# Microcontroller.net
KiCad netlist of a schematic drawn in Altium Designer
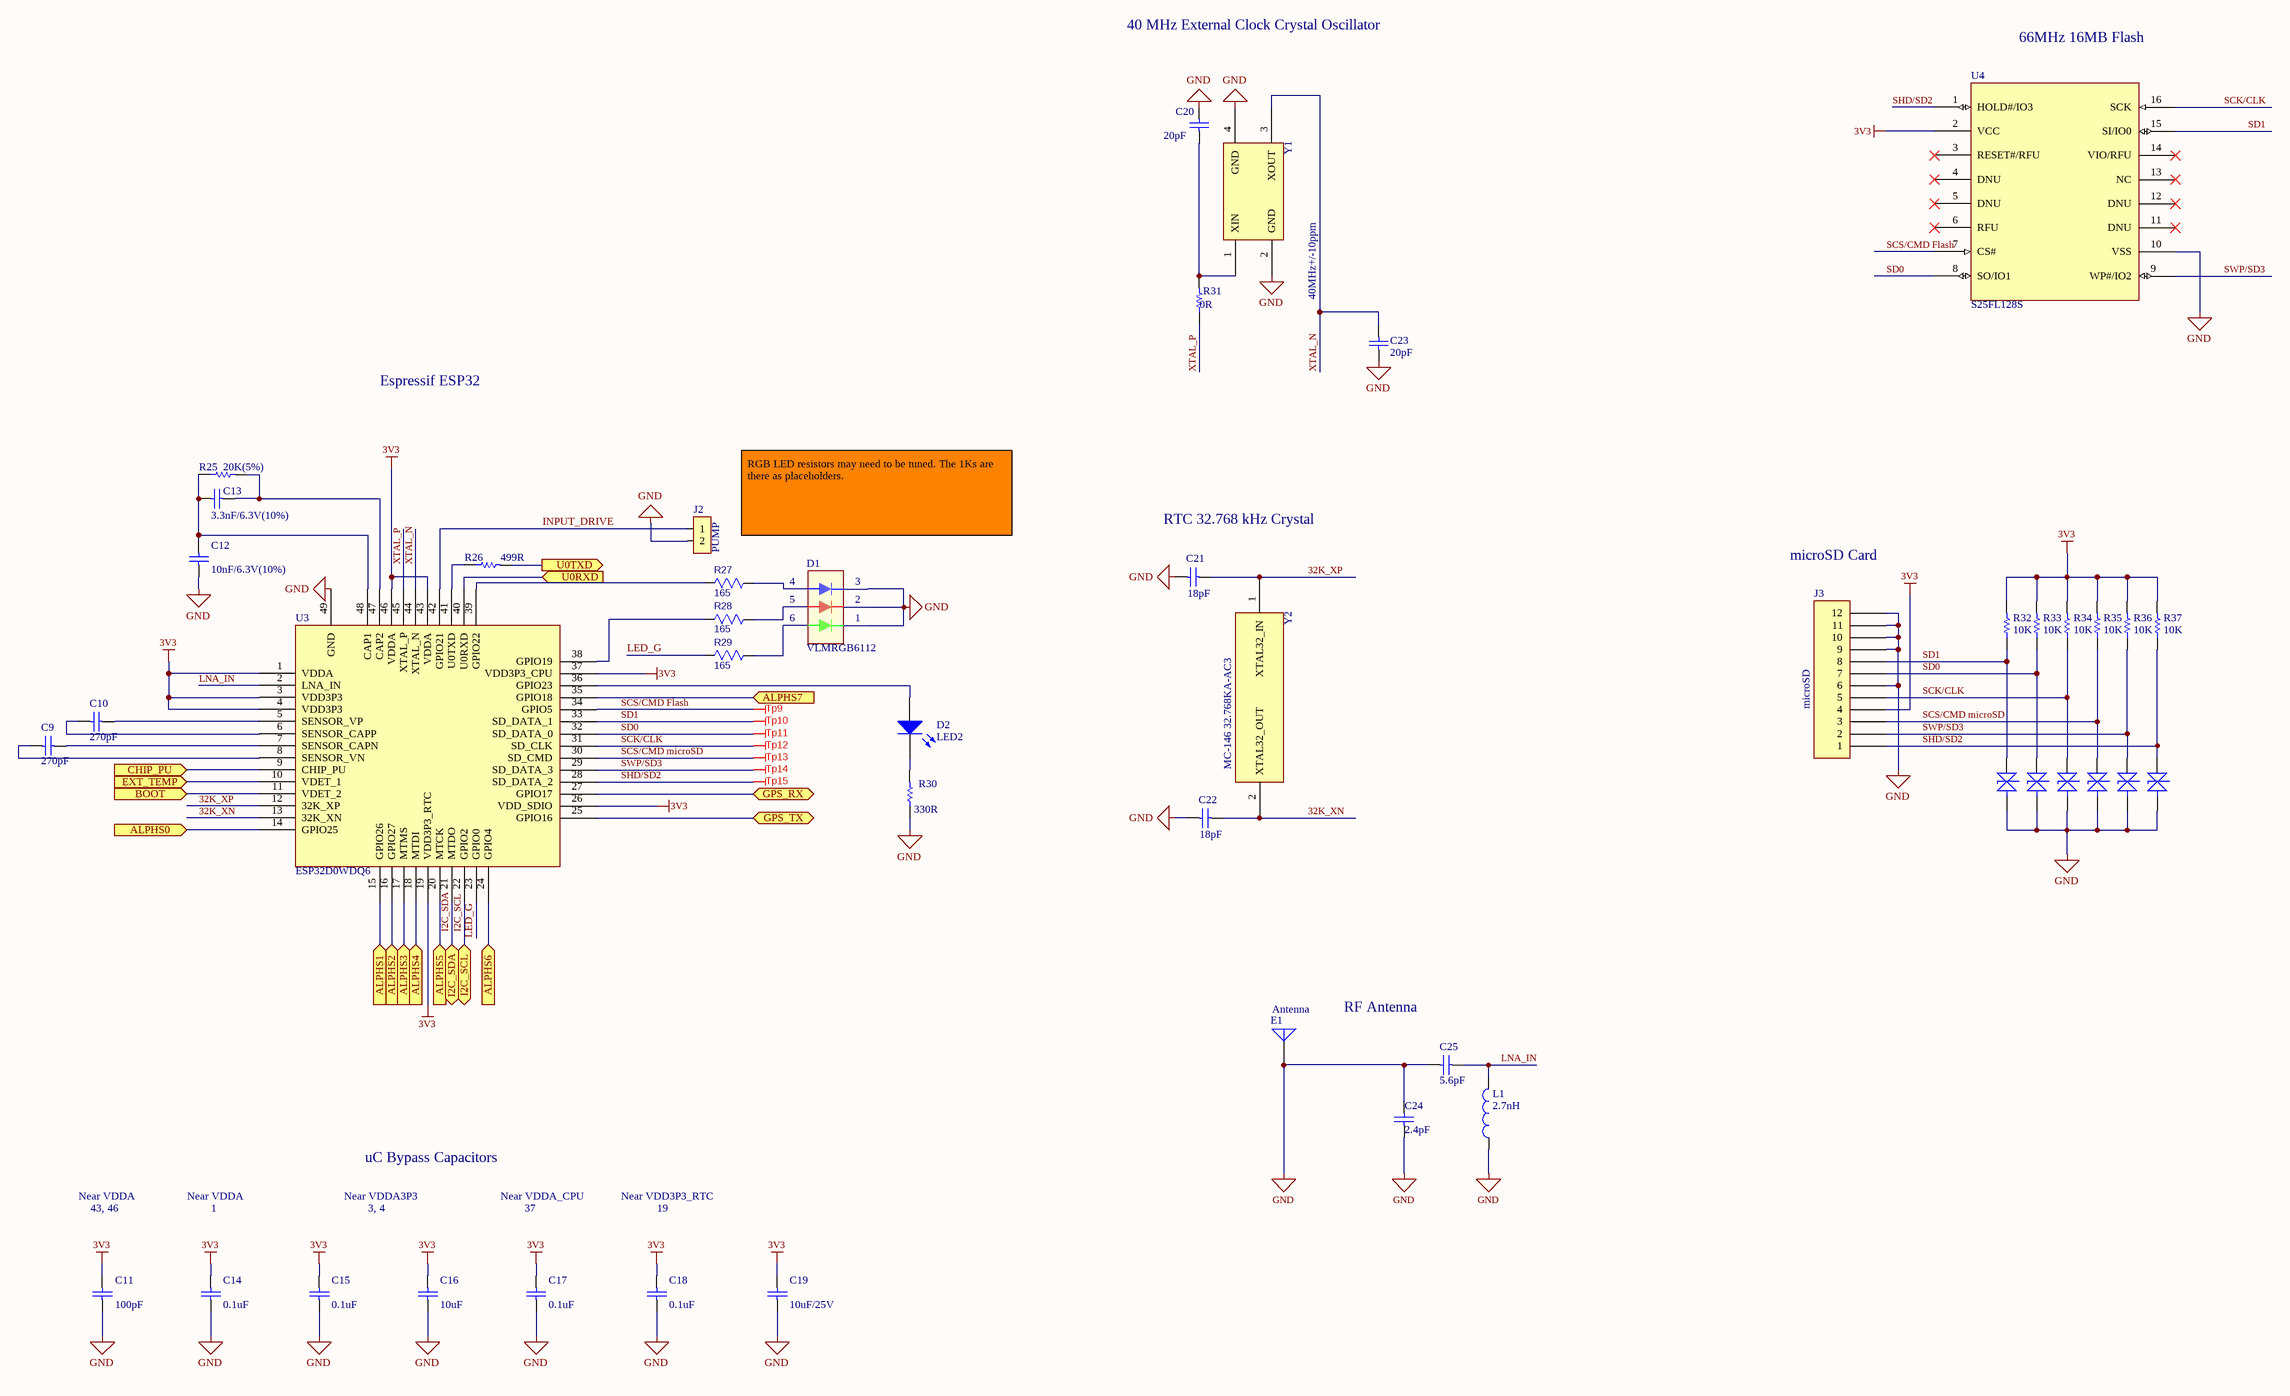
[diagram p0: Microcontroller.SchDoc]

(export (version "E")
  (design (tool "Eeschema 10.0.6"))
  (components
    (comp (ref "C9")
      (value "270pF")
      (footprint "1608[0603]")
      (description "Capacitor")
      (fields (field (name "Comment") "Cap") (field (name "PUBLISHER") "Altium Limited"))
      (libsource (lib "Miscellaneous Devices") (part "Cap"))
    )
    (comp (ref "C10")
      (value "270pF")
      (footprint "1608[0603]")
      (description "Capacitor")
      (fields (field (name "Comment") "Cap") (field (name "PUBLISHER") "Altium Limited"))
      (libsource (lib "Miscellaneous Devices") (part "Cap"))
    )
    (comp (ref "C11")
      (value "100pF")
      (footprint "1608[0603]")
      (description "Capacitor")
      (fields (field (name "Comment") "Cap") (field (name "PUBLISHER") "Altium Limited"))
      (libsource (lib "Miscellaneous Devices") (part "Cap"))
    )
    (comp (ref "C12")
      (value "10nF/6.3V(10%)")
      (footprint "1608[0603]")
      (description "Capacitor")
      (fields (field (name "Comment") "Cap") (field (name "PUBLISHER") "Altium Limited"))
      (libsource (lib "Miscellaneous Devices") (part "Cap"))
    )
    (comp (ref "C13")
      (value "3.3nF/6.3V(10%)")
      (footprint "1608[0603]")
      (description "Capacitor")
      (fields (field (name "Comment") "Cap") (field (name "PUBLISHER") "Altium Limited"))
      (libsource (lib "Miscellaneous Devices") (part "Cap"))
    )
    (comp (ref "C14")
      (value "0.1uF")
      (footprint "1608[0603]")
      (description "Capacitor")
      (fields (field (name "Comment") "Cap") (field (name "PUBLISHER") "Altium Limited"))
      (libsource (lib "Miscellaneous Devices") (part "Cap"))
    )
    (comp (ref "C15")
      (value "0.1uF")
      (footprint "1608[0603]")
      (description "Capacitor")
      (fields (field (name "Comment") "Cap") (field (name "PUBLISHER") "Altium Limited"))
      (libsource (lib "Miscellaneous Devices") (part "Cap"))
    )
    (comp (ref "C16")
      (value "10uF")
      (footprint "1608[0603]")
      (description "Capacitor")
      (fields (field (name "Comment") "Cap") (field (name "PUBLISHER") "Altium Limited"))
      (libsource (lib "Miscellaneous Devices") (part "Cap"))
    )
    (comp (ref "C17")
      (value "0.1uF")
      (footprint "1608[0603]")
      (description "Capacitor")
      (fields (field (name "Comment") "Cap") (field (name "PUBLISHER") "Altium Limited"))
      (libsource (lib "Miscellaneous Devices") (part "Cap"))
    )
    (comp (ref "C18")
      (value "0.1uF")
      (footprint "1608[0603]")
      (description "Capacitor")
      (fields (field (name "Comment") "Cap") (field (name "PUBLISHER") "Altium Limited"))
      (libsource (lib "Miscellaneous Devices") (part "Cap"))
    )
    (comp (ref "C19")
      (value "10uF/25V")
      (footprint "1608[0603]")
      (description "Capacitor")
      (fields (field (name "Comment") "Cap") (field (name "PUBLISHER") "Altium Limited"))
      (libsource (lib "Miscellaneous Devices") (part "Cap"))
    )
    (comp (ref "C20")
      (value "20pF")
      (footprint "1608[0603]")
      (description "Capacitor")
      (fields (field (name "Comment") "Cap") (field (name "PUBLISHER") "Altium Limited"))
      (libsource (lib "Miscellaneous Devices") (part "Cap"))
    )
    (comp (ref "C21")
      (value "18pF")
      (footprint "1608[0603]")
      (description "Capacitor")
      (fields (field (name "Comment") "Cap") (field (name "PUBLISHER") "Altium Limited"))
      (libsource (lib "Miscellaneous Devices") (part "Cap"))
    )
    (comp (ref "C22")
      (value "18pF")
      (footprint "1608[0603]")
      (description "Capacitor")
      (fields (field (name "Comment") "Cap") (field (name "PUBLISHER") "Altium Limited"))
      (libsource (lib "Miscellaneous Devices") (part "Cap"))
    )
    (comp (ref "C23")
      (value "20pF")
      (footprint "1608[0603]")
      (description "Capacitor")
      (fields (field (name "Comment") "Cap") (field (name "PUBLISHER") "Altium Limited"))
      (libsource (lib "Miscellaneous Devices") (part "Cap"))
    )
    (comp (ref "C24")
      (value "2.4pF")
      (footprint "1608[0603]")
      (description "Capacitor")
      (fields (field (name "Comment") "Cap") (field (name "PUBLISHER") "Altium Limited"))
      (libsource (lib "Miscellaneous Devices") (part "Cap"))
    )
    (comp (ref "C25")
      (value "5.6pF")
      (footprint "1608[0603]")
      (description "Capacitor")
      (fields (field (name "Comment") "Cap") (field (name "PUBLISHER") "Altium Limited"))
      (libsource (lib "Miscellaneous Devices") (part "Cap"))
    )
    (comp (ref "D1")
      (value "VLMRGB6112")
      (footprint "VLMRGB6112")
      (description "LED RGB Clear 624nm/526nm/469nm 2V/3.1V/3V PLCC-6")
      (fields
        (field (name "MANUFACTURER") "Vishay Semiconductor Opto Division")
        (field (name "MANUFACTURER PART NUMBER") "VLMRGB6112-00-GS08")
      )
      (libsource (lib "LEDs") (part "VLMRGB6112"))
    )
    (comp (ref "D2")
      (value "LED2")
      (footprint "3.2X1.6X1.1")
      (description "Typical RED, GREEN, YELLOW, AMBER GaAs LED")
      (fields (field (name "PUBLISHER") "Altium Limited"))
      (libsource (lib "Miscellaneous Devices") (part "LED2"))
    )
    (comp (ref "D3")
      (value "ESD7951ST5GOSCT-ND")
      (footprint "SODFL100X40-2N")
      (description "TVS Diode")
      (libsource (lib "Gas Monitor Components") (part "ESD7951S"))
    )
    (comp (ref "D4")
      (value "ESD7951ST5GOSCT-ND")
      (footprint "SODFL100X40-2N")
      (description "TVS Diode")
      (libsource (lib "Gas Monitor Components") (part "ESD7951S"))
    )
    (comp (ref "D5")
      (value "ESD7951ST5GOSCT-ND")
      (footprint "SODFL100X40-2N")
      (description "TVS Diode")
      (libsource (lib "Gas Monitor Components") (part "ESD7951S"))
    )
    (comp (ref "D6")
      (value "ESD7951ST5GOSCT-ND")
      (footprint "SODFL100X40-2N")
      (description "TVS Diode")
      (libsource (lib "Gas Monitor Components") (part "ESD7951S"))
    )
    (comp (ref "D7")
      (value "ESD7951ST5GOSCT-ND")
      (footprint "SODFL100X40-2N")
      (description "TVS Diode")
      (libsource (lib "Gas Monitor Components") (part "ESD7951S"))
    )
    (comp (ref "D8")
      (value "ESD7951ST5GOSCT-ND")
      (footprint "SODFL100X40-2N")
      (description "TVS Diode")
      (libsource (lib "Gas Monitor Components") (part "ESD7951S"))
    )
    (comp (ref "E1")
      (value "Antenna")
      (footprint "SWRA1117")
      (description "Generic Antenna")
      (fields (field (name "PUBLISHER") "Altium Limited"))
      (libsource (lib "Miscellaneous Devices") (part "Antenna"))
    )
    (comp (ref "J2")
      (value "PUMP")
      (footprint "6410/2pin")
      (description "Connector 2 pin")
      (libsource (lib "VolcDB") (part "CON2"))
    )
    (comp (ref "J3")
      (value "microSD")
      (footprint "SD-47219-001")
      (libsource (lib "Gas Monitor Components") (part "CON12"))
    )
    (comp (ref "L1")
      (value "2.7nH")
      (footprint "INDC1608L")
      (description "Inductor")
      (fields (field (name "PUBLISHER") "Altium Limited"))
      (libsource (lib "Miscellaneous Devices") (part "Inductor"))
    )
    (comp (ref "R25")
      (value "20K(5%)")
      (footprint "6-0805_N")
      (description "Resistor")
      (fields (field (name "Comment") "Res1") (field (name "PUBLISHER") "Altium Limited"))
      (libsource (lib "Miscellaneous Devices") (part "Res1"))
    )
    (comp (ref "R26")
      (value "499R")
      (footprint "6-0805_L")
      (description "Resistor")
      (fields (field (name "Comment") "Res1") (field (name "PUBLISHER") "Altium Limited"))
      (libsource (lib "Miscellaneous Devices") (part "Res1"))
    )
    (comp (ref "R27")
      (value "165")
      (footprint "R1608[0603] small")
      (description "RES 1K Ohm ±5%, 0.25W,1/4W 0603")
      (fields (field (name "MANUFACTURER") "Rohm") (field (name "MANUFACTURER PART NUMBER") "ESR03EZPJ102"))
      (libsource (lib "Resistors") (part "1K00_0603_0.1W"))
    )
    (comp (ref "R28")
      (value "165")
      (footprint "R1608[0603] small")
      (description "RES 1K Ohm ±5%, 0.25W,1/4W 0603")
      (fields (field (name "MANUFACTURER") "Rohm") (field (name "MANUFACTURER PART NUMBER") "ESR03EZPJ102"))
      (libsource (lib "Resistors") (part "1K00_0603_0.1W"))
    )
    (comp (ref "R29")
      (value "165")
      (footprint "R1608[0603] small")
      (description "RES 1K Ohm ±5%, 0.25W,1/4W 0603")
      (fields (field (name "MANUFACTURER") "Rohm") (field (name "MANUFACTURER PART NUMBER") "ESR03EZPJ102"))
      (libsource (lib "Resistors") (part "1K00_0603_0.1W"))
    )
    (comp (ref "R30")
      (value "330R")
      (footprint "6-0805_N")
      (description "Resistor")
      (fields (field (name "Comment") "Res1") (field (name "PUBLISHER") "Altium Limited"))
      (libsource (lib "Miscellaneous Devices") (part "Res1"))
    )
    (comp (ref "R31")
      (value "0R")
      (footprint "6-0805_N")
      (description "Resistor")
      (fields (field (name "Comment") "Res1") (field (name "PUBLISHER") "Altium Limited"))
      (libsource (lib "Miscellaneous Devices") (part "Res1"))
    )
    (comp (ref "R32")
      (value "10K")
      (footprint "6-0805_N")
      (description "Resistor")
      (fields (field (name "Comment") "Res1") (field (name "PUBLISHER") "Altium Limited"))
      (libsource (lib "Miscellaneous Devices") (part "Res1"))
    )
    (comp (ref "R33")
      (value "10K")
      (footprint "6-0805_N")
      (description "Resistor")
      (fields (field (name "Comment") "Res1") (field (name "PUBLISHER") "Altium Limited"))
      (libsource (lib "Miscellaneous Devices") (part "Res1"))
    )
    (comp (ref "R34")
      (value "10K")
      (footprint "6-0805_N")
      (description "Resistor")
      (fields (field (name "Comment") "Res1") (field (name "PUBLISHER") "Altium Limited"))
      (libsource (lib "Miscellaneous Devices") (part "Res1"))
    )
    (comp (ref "R35")
      (value "10K")
      (footprint "6-0805_N")
      (description "Resistor")
      (fields (field (name "Comment") "Res1") (field (name "PUBLISHER") "Altium Limited"))
      (libsource (lib "Miscellaneous Devices") (part "Res1"))
    )
    (comp (ref "R36")
      (value "10K")
      (footprint "6-0805_N")
      (description "Resistor")
      (fields (field (name "Comment") "Res1") (field (name "PUBLISHER") "Altium Limited"))
      (libsource (lib "Miscellaneous Devices") (part "Res1"))
    )
    (comp (ref "R37")
      (value "10K")
      (footprint "6-0805_N")
      (description "Resistor")
      (fields (field (name "Comment") "Res1") (field (name "PUBLISHER") "Altium Limited"))
      (libsource (lib "Miscellaneous Devices") (part "Res1"))
    )
    (comp (ref "Tp9")
      (value "PAD")
      (footprint "TP_SMD_45MIL")
      (description "SMD Test Pad")
      (fields (field (name "MANUFACTURER") "No P/N Required"))
      (libsource (lib "Connectors") (part "TP_SMD_45MIL"))
    )
    (comp (ref "Tp10")
      (value "PAD")
      (footprint "TP_SMD_45MIL")
      (description "SMD Test Pad")
      (fields (field (name "MANUFACTURER") "No P/N Required"))
      (libsource (lib "Connectors") (part "TP_SMD_45MIL"))
    )
    (comp (ref "Tp11")
      (value "PAD")
      (footprint "TP_SMD_45MIL")
      (description "SMD Test Pad")
      (fields (field (name "MANUFACTURER") "No P/N Required"))
      (libsource (lib "Connectors") (part "TP_SMD_45MIL"))
    )
    (comp (ref "Tp12")
      (value "PAD")
      (footprint "TP_SMD_45MIL")
      (description "SMD Test Pad")
      (fields (field (name "MANUFACTURER") "No P/N Required"))
      (libsource (lib "Connectors") (part "TP_SMD_45MIL"))
    )
    (comp (ref "Tp13")
      (value "PAD")
      (footprint "TP_SMD_45MIL")
      (description "SMD Test Pad")
      (fields (field (name "MANUFACTURER") "No P/N Required"))
      (libsource (lib "Connectors") (part "TP_SMD_45MIL"))
    )
    (comp (ref "Tp14")
      (value "PAD")
      (footprint "TP_SMD_45MIL")
      (description "SMD Test Pad")
      (fields (field (name "MANUFACTURER") "No P/N Required"))
      (libsource (lib "Connectors") (part "TP_SMD_45MIL"))
    )
    (comp (ref "Tp15")
      (value "PAD")
      (footprint "TP_SMD_45MIL")
      (description "SMD Test Pad")
      (fields (field (name "MANUFACTURER") "No P/N Required"))
      (libsource (lib "Connectors") (part "TP_SMD_45MIL"))
    )
    (comp (ref "U3")
      (value "ESP32D0WDQ6")
      (footprint "QFN40P600X600X90_HS-49N")
      (description "Microcontroller")
      (libsource (lib "Gas Monitor Components") (part "ESP32"))
    )
    (comp (ref "U4")
      (value "S25FL128S")
      (footprint "SOIC127P1030X265-16N")
      (description "QSPI 128M Flash Memory")
      (libsource (lib "Gas Monitor Components") (part "S25FL128S"))
    )
    (comp (ref "Y1")
      (value "FA-20H")
      (footprint "FA-20H")
      (description "40MHz Crystal Oscillator")
      (libsource (lib "Gas Monitor Components") (part "Y1"))
    )
    (comp (ref "Y2")
      (value "MC-146 32.768KA-AC3")
      (footprint "MC-146")
      (description "32.768 kHz Crystal")
      (libsource (lib "Gas Monitor Components") (part "MC-146 32.768KA-AC3"))
    )
  )
  (nets
    (net (code "1") (name "/32K_XN") (class "Default")
      (node (ref "C22") (pin "2") (pinfunction "2_2") (pintype "passive"))
      (node (ref "U3") (pin "13") (pinfunction "32K_XN_13") (pintype "passive"))
      (node (ref "Y2") (pin "2") (pinfunction "XTAL32_OUT_2") (pintype "passive"))
    )
    (net (code "2") (name "/32K_XP") (class "Default")
      (node (ref "C21") (pin "2") (pinfunction "2_2") (pintype "passive"))
      (node (ref "U3") (pin "12") (pinfunction "32K_XP_12") (pintype "passive"))
      (node (ref "Y2") (pin "1") (pinfunction "XTAL32_IN_1") (pintype "passive"))
    )
    (net (code "3") (name "/ALPHS0") (class "Default")
      (node (ref "U3") (pin "14") (pinfunction "GPIO25_14") (pintype "passive"))
    )
    (net (code "4") (name "/ALPHS1") (class "Default")
      (node (ref "U3") (pin "15") (pinfunction "GPIO26_15") (pintype "passive"))
    )
    (net (code "5") (name "/ALPHS2") (class "Default")
      (node (ref "U3") (pin "16") (pinfunction "GPIO27_16") (pintype "passive"))
    )
    (net (code "6") (name "/ALPHS3") (class "Default")
      (node (ref "U3") (pin "17") (pinfunction "MTMS_17") (pintype "passive"))
    )
    (net (code "7") (name "/ALPHS4") (class "Default")
      (node (ref "U3") (pin "18") (pinfunction "MTDI_18") (pintype "passive"))
    )
    (net (code "8") (name "/ALPHS5") (class "Default")
      (node (ref "U3") (pin "20") (pinfunction "MTCK_20") (pintype "passive"))
    )
    (net (code "9") (name "/ALPHS6") (class "Default")
      (node (ref "U3") (pin "24") (pinfunction "GPIO4_24") (pintype "passive"))
    )
    (net (code "10") (name "/ALPHS7") (class "Default")
      (node (ref "U3") (pin "35") (pinfunction "GPIO18_35") (pintype "passive"))
    )
    (net (code "11") (name "/BOOT") (class "Default")
      (node (ref "U3") (pin "11") (pinfunction "VDET_2_11") (pintype "passive"))
    )
    (net (code "12") (name "/CHIP_PU") (class "Default")
      (node (ref "U3") (pin "9") (pinfunction "CHIP_PU_9") (pintype "passive"))
    )
    (net (code "13") (name "/EXT_TEMP") (class "Default")
      (node (ref "U3") (pin "10") (pinfunction "VDET_1_10") (pintype "passive"))
    )
    (net (code "14") (name "/GPS_RX") (class "Default")
      (node (ref "U3") (pin "27") (pinfunction "GPIO17_27") (pintype "passive"))
    )
    (net (code "15") (name "/GPS_TX") (class "Default")
      (node (ref "U3") (pin "25") (pinfunction "GPIO16_25") (pintype "passive"))
    )
    (net (code "16") (name "/I2C_SCL") (class "Default")
      (node (ref "U3") (pin "22") (pinfunction "GPIO2_22") (pintype "passive"))
    )
    (net (code "17") (name "/I2C_SDA") (class "Default")
      (node (ref "U3") (pin "21") (pinfunction "MTDO_21") (pintype "passive"))
    )
    (net (code "18") (name "/INPUT_DRIVE") (class "Default")
      (node (ref "J2") (pin "1") (pinfunction "1_1") (pintype "passive"))
      (node (ref "U3") (pin "42") (pinfunction "GPIO21_42") (pintype "passive"))
    )
    (net (code "19") (name "/LED_G") (class "Default")
      (node (ref "R29") (pin "1") (pintype "passive"))
      (node (ref "U3") (pin "23") (pinfunction "GPIO0_23") (pintype "passive"))
    )
    (net (code "20") (name "/LNA_IN") (class "Default")
      (node (ref "C25") (pin "1") (pinfunction "1_1") (pintype "passive"))
      (node (ref "L1") (pin "2") (pinfunction "2_2") (pintype "passive"))
      (node (ref "U3") (pin "2") (pinfunction "LNA_IN_2") (pintype "passive"))
    )
    (net (code "21") (name "/SCK{slash}CLK") (class "Default")
      (node (ref "D5") (pin "2") (pinfunction "ANODE_2") (pintype "passive"))
      (node (ref "J3") (pin "5") (pinfunction "5_5") (pintype "passive"))
      (node (ref "R34") (pin "1") (pinfunction "1_1") (pintype "passive"))
      (node (ref "Tp12") (pin "1") (pintype "passive"))
      (node (ref "U3") (pin "31") (pinfunction "SD_CLK_31") (pintype "passive"))
      (node (ref "U4") (pin "16") (pinfunction "SCK_16") (pintype "input"))
    )
    (net (code "22") (name "/SCS{slash}CMD Flash") (class "Default")
      (node (ref "Tp9") (pin "1") (pintype "passive"))
      (node (ref "U3") (pin "34") (pinfunction "GPIO5_34") (pintype "passive"))
      (node (ref "U4") (pin "7") (pinfunction "CS#_7") (pintype "input"))
    )
    (net (code "23") (name "/SCS{slash}CMD microSD") (class "Default")
      (node (ref "D6") (pin "2") (pinfunction "ANODE_2") (pintype "passive"))
      (node (ref "J3") (pin "3") (pinfunction "3_3") (pintype "passive"))
      (node (ref "R35") (pin "1") (pinfunction "1_1") (pintype "passive"))
      (node (ref "Tp13") (pin "1") (pintype "passive"))
      (node (ref "U3") (pin "30") (pinfunction "SD_CMD_30") (pintype "passive"))
    )
    (net (code "24") (name "/SD0") (class "Default")
      (node (ref "D4") (pin "2") (pinfunction "ANODE_2") (pintype "passive"))
      (node (ref "J3") (pin "7") (pinfunction "7_7") (pintype "passive"))
      (node (ref "R33") (pin "1") (pinfunction "1_1") (pintype "passive"))
      (node (ref "Tp11") (pin "1") (pintype "passive"))
      (node (ref "U3") (pin "32") (pinfunction "SD_DATA_0_32") (pintype "passive"))
      (node (ref "U4") (pin "8") (pinfunction "SO/IO1_8") (pintype "bidirectional"))
    )
    (net (code "25") (name "/SD1") (class "Default")
      (node (ref "D3") (pin "2") (pinfunction "ANODE_2") (pintype "passive"))
      (node (ref "J3") (pin "8") (pinfunction "8_8") (pintype "passive"))
      (node (ref "R32") (pin "1") (pinfunction "1_1") (pintype "passive"))
      (node (ref "Tp10") (pin "1") (pintype "passive"))
      (node (ref "U3") (pin "33") (pinfunction "SD_DATA_1_33") (pintype "passive"))
      (node (ref "U4") (pin "15") (pinfunction "SI/IO0_15") (pintype "bidirectional"))
    )
    (net (code "26") (name "/SHD{slash}SD2") (class "Default")
      (node (ref "D8") (pin "2") (pinfunction "ANODE_2") (pintype "passive"))
      (node (ref "J3") (pin "1") (pinfunction "1_1") (pintype "passive"))
      (node (ref "R37") (pin "1") (pinfunction "1_1") (pintype "passive"))
      (node (ref "Tp15") (pin "1") (pintype "passive"))
      (node (ref "U3") (pin "28") (pinfunction "SD_DATA_2_28") (pintype "passive"))
      (node (ref "U4") (pin "1") (pinfunction "HOLD#/IO3_1") (pintype "bidirectional"))
    )
    (net (code "27") (name "/SWP{slash}SD3") (class "Default")
      (node (ref "D7") (pin "2") (pinfunction "ANODE_2") (pintype "passive"))
      (node (ref "J3") (pin "2") (pinfunction "2_2") (pintype "passive"))
      (node (ref "R36") (pin "1") (pinfunction "1_1") (pintype "passive"))
      (node (ref "Tp14") (pin "1") (pintype "passive"))
      (node (ref "U3") (pin "29") (pinfunction "SD_DATA_3_29") (pintype "passive"))
      (node (ref "U4") (pin "9") (pinfunction "WP#/IO2_9") (pintype "bidirectional"))
    )
    (net (code "28") (name "/U0RXD") (class "Default")
      (node (ref "U3") (pin "40") (pinfunction "U0RXD_40") (pintype "passive"))
    )
    (net (code "29") (name "/U0TXD") (class "Default")
      (node (ref "R26") (pin "2") (pinfunction "2_2") (pintype "passive"))
    )
    (net (code "30") (name "/XTAL_N") (class "Default")
      (node (ref "C23") (pin "1") (pinfunction "1_1") (pintype "passive"))
      (node (ref "U3") (pin "44") (pinfunction "XTAL_N_44") (pintype "passive"))
      (node (ref "Y1") (pin "3") (pinfunction "XOUT_3") (pintype "passive"))
    )
    (net (code "31") (name "/XTAL_P") (class "Default")
      (node (ref "R31") (pin "1") (pinfunction "1_1") (pintype "passive"))
      (node (ref "U3") (pin "45") (pinfunction "XTAL_P_45") (pintype "passive"))
    )
    (net (code "32") (name "3V3") (class "Default")
      (node (ref "C11") (pin "2") (pinfunction "2_2") (pintype "passive"))
      (node (ref "C14") (pin "2") (pinfunction "2_2") (pintype "passive"))
      (node (ref "C15") (pin "2") (pinfunction "2_2") (pintype "passive"))
      (node (ref "C16") (pin "2") (pinfunction "2_2") (pintype "passive"))
      (node (ref "C17") (pin "2") (pinfunction "2_2") (pintype "passive"))
      (node (ref "C18") (pin "2") (pinfunction "2_2") (pintype "passive"))
      (node (ref "C19") (pin "2") (pinfunction "2_2") (pintype "passive"))
      (node (ref "J3") (pin "4") (pinfunction "4_4") (pintype "passive"))
      (node (ref "R32") (pin "2") (pinfunction "2_2") (pintype "passive"))
      (node (ref "R33") (pin "2") (pinfunction "2_2") (pintype "passive"))
      (node (ref "R34") (pin "2") (pinfunction "2_2") (pintype "passive"))
      (node (ref "R35") (pin "2") (pinfunction "2_2") (pintype "passive"))
      (node (ref "R36") (pin "2") (pinfunction "2_2") (pintype "passive"))
      (node (ref "R37") (pin "2") (pinfunction "2_2") (pintype "passive"))
      (node (ref "U3") (pin "1") (pinfunction "VDDA_1") (pintype "power_in"))
      (node (ref "U3") (pin "19") (pinfunction "VDD3P3_RTC_19") (pintype "passive"))
      (node (ref "U3") (pin "26") (pinfunction "VDD_SDIO_26") (pintype "passive"))
      (node (ref "U3") (pin "3") (pinfunction "VDD3P3_3") (pintype "power_in"))
      (node (ref "U3") (pin "37") (pinfunction "VDD3P3_CPU_37") (pintype "passive"))
      (node (ref "U3") (pin "4") (pinfunction "VDD3P3_4") (pintype "passive"))
      (node (ref "U3") (pin "43") (pinfunction "VDDA_43") (pintype "power_in"))
      (node (ref "U3") (pin "46") (pinfunction "VDDA_46") (pintype "power_in"))
      (node (ref "U4") (pin "2") (pinfunction "VCC_2") (pintype "power_in"))
    )
    (net (code "33") (name "GND") (class "Default")
      (node (ref "C11") (pin "1") (pinfunction "1_1") (pintype "passive"))
      (node (ref "C12") (pin "1") (pinfunction "1_1") (pintype "passive"))
      (node (ref "C14") (pin "1") (pinfunction "1_1") (pintype "passive"))
      (node (ref "C15") (pin "1") (pinfunction "1_1") (pintype "passive"))
      (node (ref "C16") (pin "1") (pinfunction "1_1") (pintype "passive"))
      (node (ref "C17") (pin "1") (pinfunction "1_1") (pintype "passive"))
      (node (ref "C18") (pin "1") (pinfunction "1_1") (pintype "passive"))
      (node (ref "C19") (pin "1") (pinfunction "1_1") (pintype "passive"))
      (node (ref "C20") (pin "2") (pinfunction "2_2") (pintype "passive"))
      (node (ref "C21") (pin "1") (pinfunction "1_1") (pintype "passive"))
      (node (ref "C22") (pin "1") (pinfunction "1_1") (pintype "passive"))
      (node (ref "C23") (pin "2") (pinfunction "2_2") (pintype "passive"))
      (node (ref "C24") (pin "1") (pinfunction "1_1") (pintype "passive"))
      (node (ref "C24") (pin "2") (pinfunction "2_2") (pintype "passive"))
      (node (ref "C25") (pin "2") (pinfunction "2_2") (pintype "passive"))
      (node (ref "D1") (pin "1") (pinfunction "A2_1") (pintype "passive"))
      (node (ref "D1") (pin "2") (pinfunction "C3_2") (pintype "passive"))
      (node (ref "D1") (pin "3") (pinfunction "A3_3") (pintype "passive"))
      (node (ref "D3") (pin "1") (pinfunction "CATHODE_1") (pintype "passive"))
      (node (ref "D4") (pin "1") (pinfunction "CATHODE_1") (pintype "passive"))
      (node (ref "D5") (pin "1") (pinfunction "CATHODE_1") (pintype "passive"))
      (node (ref "D6") (pin "1") (pinfunction "CATHODE_1") (pintype "passive"))
      (node (ref "D7") (pin "1") (pinfunction "CATHODE_1") (pintype "passive"))
      (node (ref "D8") (pin "1") (pinfunction "CATHODE_1") (pintype "passive"))
      (node (ref "E1") (pin "1") (pinfunction "A_1") (pintype "passive"))
      (node (ref "J2") (pin "2") (pinfunction "2_2") (pintype "passive"))
      (node (ref "J3") (pin "10") (pinfunction "10_10") (pintype "passive"))
      (node (ref "J3") (pin "11") (pinfunction "11_11") (pintype "passive"))
      (node (ref "J3") (pin "12") (pinfunction "12_12") (pintype "passive"))
      (node (ref "J3") (pin "6") (pinfunction "6_6") (pintype "passive"))
      (node (ref "J3") (pin "9") (pinfunction "9_9") (pintype "passive"))
      (node (ref "L1") (pin "1") (pinfunction "1_1") (pintype "passive"))
      (node (ref "R30") (pin "1") (pinfunction "1_1") (pintype "passive"))
      (node (ref "U3") (pin "49") (pinfunction "GND_49") (pintype "power_in"))
      (node (ref "U4") (pin "10") (pinfunction "VSS_10") (pintype "power_in"))
      (node (ref "Y1") (pin "2") (pinfunction "GND_2") (pintype "power_in"))
      (node (ref "Y1") (pin "4") (pinfunction "GND_4") (pintype "power_in"))
    )
    (net (code "34") (name "Net-(D1-C1-Pad4)") (class "Default")
      (node (ref "D1") (pin "4") (pinfunction "C1_4") (pintype "passive"))
      (node (ref "R27") (pin "2") (pintype "passive"))
    )
    (net (code "35") (name "Net-(D1-C1-Pad5)") (class "Default")
      (node (ref "D1") (pin "5") (pinfunction "C1_5") (pintype "passive"))
      (node (ref "R28") (pin "2") (pintype "passive"))
    )
    (net (code "36") (name "Net-(D1-C1-Pad6)") (class "Default")
      (node (ref "D1") (pin "6") (pinfunction "C1_6") (pintype "passive"))
      (node (ref "R29") (pin "2") (pintype "passive"))
    )
    (net (code "37") (name "Net-(D2-A)") (class "Default")
      (node (ref "D2") (pin "1") (pinfunction "A_1") (pintype "passive"))
      (node (ref "U3") (pin "36") (pinfunction "GPIO23_36") (pintype "passive"))
    )
    (net (code "38") (name "Net-(D2-K)") (class "Default")
      (node (ref "D2") (pin "2") (pinfunction "K_2") (pintype "passive"))
      (node (ref "R30") (pin "2") (pinfunction "2_2") (pintype "passive"))
    )
    (net (code "39") (name "Net-(U3-CAP1)") (class "Default")
      (node (ref "C12") (pin "2") (pinfunction "2_2") (pintype "passive"))
      (node (ref "C13") (pin "2") (pinfunction "2_2") (pintype "passive"))
      (node (ref "R25") (pin "1") (pinfunction "1_1") (pintype "passive"))
      (node (ref "U3") (pin "48") (pinfunction "CAP1_48") (pintype "passive"))
    )
    (net (code "40") (name "Net-(U3-CAP2)") (class "Default")
      (node (ref "C13") (pin "1") (pinfunction "1_1") (pintype "passive"))
      (node (ref "R25") (pin "2") (pinfunction "2_2") (pintype "passive"))
      (node (ref "U3") (pin "47") (pinfunction "CAP2_47") (pintype "passive"))
    )
    (net (code "41") (name "Net-(U3-GPIO19)") (class "Default")
      (node (ref "R28") (pin "1") (pintype "passive"))
      (node (ref "U3") (pin "38") (pinfunction "GPIO19_38") (pintype "passive"))
    )
    (net (code "42") (name "Net-(U3-GPIO22)") (class "Default")
      (node (ref "R27") (pin "1") (pintype "passive"))
      (node (ref "U3") (pin "39") (pinfunction "GPIO22_39") (pintype "passive"))
    )
    (net (code "43") (name "Net-(U3-SENSOR_CAPN)") (class "Default")
      (node (ref "C9") (pin "2") (pinfunction "2_2") (pintype "passive"))
      (node (ref "U3") (pin "7") (pinfunction "SENSOR_CAPN_7") (pintype "passive"))
    )
    (net (code "44") (name "Net-(U3-SENSOR_CAPP)") (class "Default")
      (node (ref "C10") (pin "2") (pinfunction "2_2") (pintype "passive"))
      (node (ref "U3") (pin "6") (pinfunction "SENSOR_CAPP_6") (pintype "passive"))
    )
    (net (code "45") (name "Net-(U3-SENSOR_VN)") (class "Default")
      (node (ref "C9") (pin "1") (pinfunction "1_1") (pintype "passive"))
      (node (ref "U3") (pin "8") (pinfunction "SENSOR_VN_8") (pintype "passive"))
    )
    (net (code "46") (name "Net-(U3-SENSOR_VP)") (class "Default")
      (node (ref "C10") (pin "1") (pinfunction "1_1") (pintype "passive"))
      (node (ref "U3") (pin "5") (pinfunction "SENSOR_VP_5") (pintype "passive"))
    )
    (net (code "47") (name "Net-(U3-U0TXD)") (class "Default")
      (node (ref "R26") (pin "1") (pinfunction "1_1") (pintype "passive"))
      (node (ref "U3") (pin "41") (pinfunction "U0TXD_41") (pintype "passive"))
    )
    (net (code "48") (name "Net-(Y1-XIN)") (class "Default")
      (node (ref "C20") (pin "1") (pinfunction "1_1") (pintype "passive"))
      (node (ref "R31") (pin "2") (pinfunction "2_2") (pintype "passive"))
      (node (ref "Y1") (pin "1") (pinfunction "XIN_1") (pintype "passive"))
    )
    (net (code "49") (name "unconnected-(U4-DNU-Pad4)") (class "Default")
      (node (ref "U4") (pin "4") (pinfunction "DNU_4") (pintype "passive+no_connect"))
    )
    (net (code "50") (name "unconnected-(U4-DNU-Pad5)") (class "Default")
      (node (ref "U4") (pin "5") (pinfunction "DNU_5") (pintype "passive+no_connect"))
    )
    (net (code "51") (name "unconnected-(U4-DNU-Pad11)") (class "Default")
      (node (ref "U4") (pin "11") (pinfunction "DNU_11") (pintype "passive+no_connect"))
    )
    (net (code "52") (name "unconnected-(U4-DNU-Pad12)") (class "Default")
      (node (ref "U4") (pin "12") (pinfunction "DNU_12") (pintype "passive+no_connect"))
    )
    (net (code "53") (name "unconnected-(U4-NC-Pad13)") (class "Default")
      (node (ref "U4") (pin "13") (pinfunction "NC_13") (pintype "passive+no_connect"))
    )
    (net (code "54") (name "unconnected-(U4-RESET#{slash}RFU-Pad3)") (class "Default")
      (node (ref "U4") (pin "3") (pinfunction "RESET#/RFU_3") (pintype "passive+no_connect"))
    )
    (net (code "55") (name "unconnected-(U4-RFU-Pad6)") (class "Default")
      (node (ref "U4") (pin "6") (pinfunction "RFU_6") (pintype "passive+no_connect"))
    )
    (net (code "56") (name "unconnected-(U4-VIO{slash}RFU-Pad14)") (class "Default")
      (node (ref "U4") (pin "14") (pinfunction "VIO/RFU_14") (pintype "power_in+no_connect"))
    )
  )
)
